# RFID_MODULE_S01.net
KiCad netlist of a schematic drawn in Altium Designer
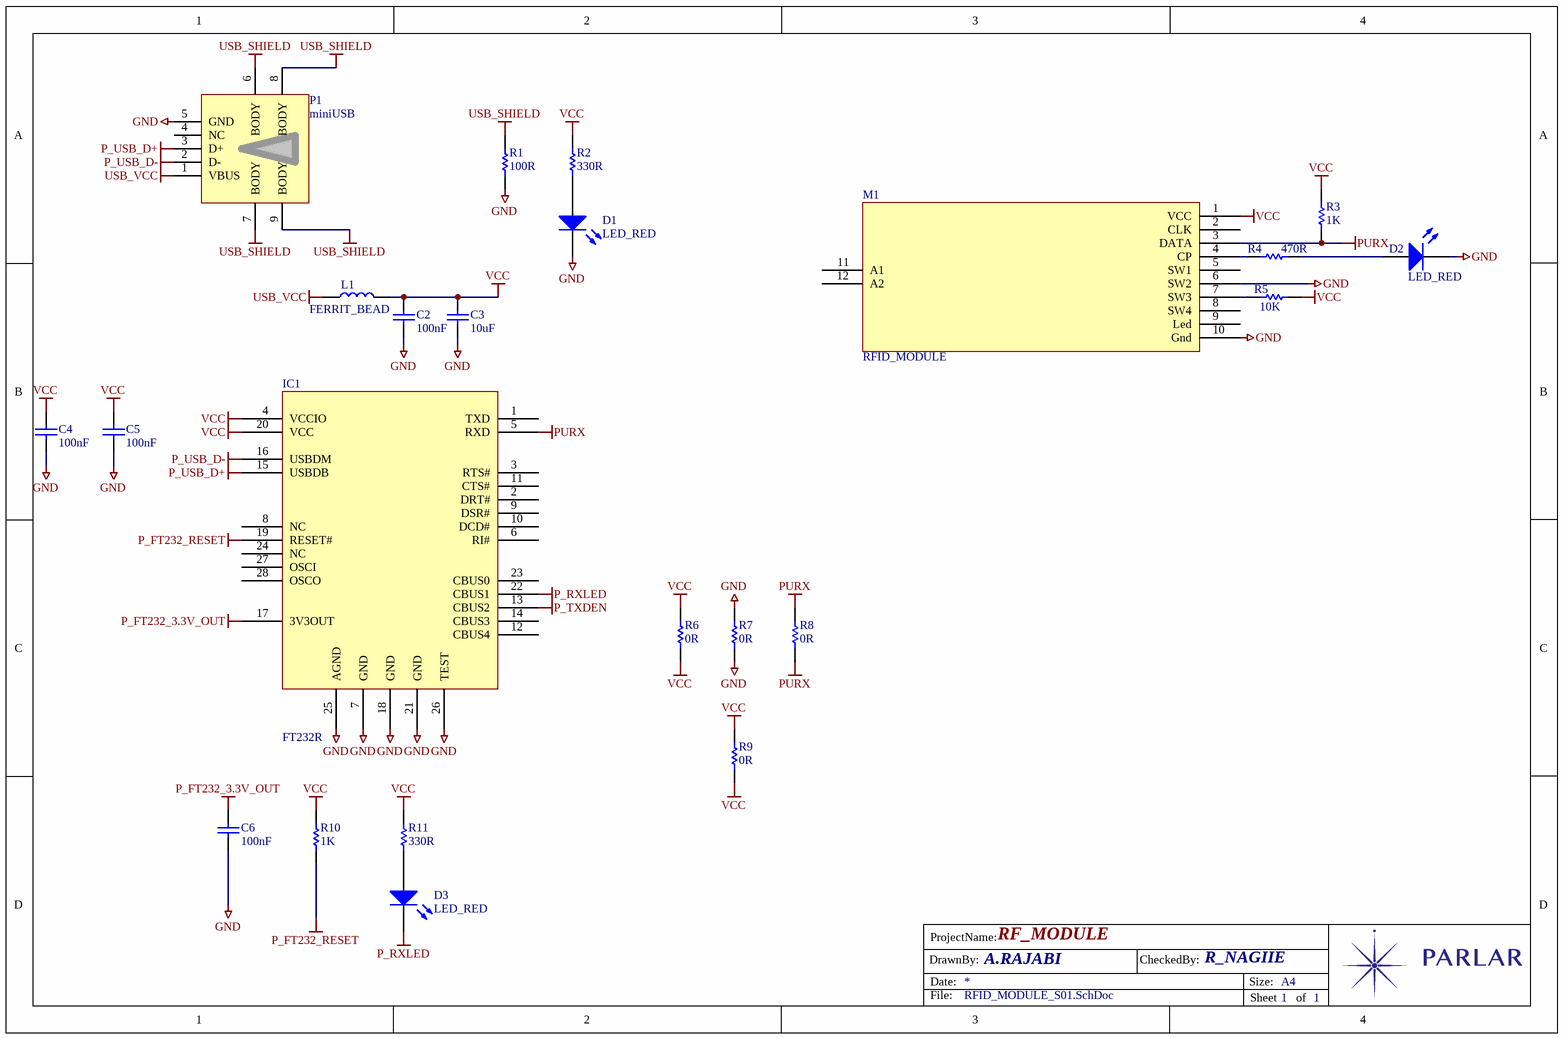
[diagram p0: RFID_MODULE_S01.SchDoc]

(export (version "E")
  (design (tool "Eeschema 10.0.6"))
  (components
    (comp (ref "C2")
      (value "100nF")
      (footprint "SMD 0805")
      (description "Capacitor")
      (fields (field (name "PUBLISHER") "Altium Limited"))
      (libsource (lib "Parlarlib_23") (part "CAP"))
    )
    (comp (ref "C3")
      (value "10uF")
      (footprint "SMD 0805")
      (description "Capacitor")
      (fields (field (name "PUBLISHER") "Altium Limited"))
      (libsource (lib "Parlarlib_23") (part "CAP"))
    )
    (comp (ref "C4")
      (value "100nF")
      (footprint "SMD 0805")
      (description "Capacitor")
      (fields (field (name "PUBLISHER") "Altium Limited"))
      (libsource (lib "Parlarlib_23") (part "CAP"))
    )
    (comp (ref "C5")
      (value "100nF")
      (footprint "SMD 1206")
      (description "Capacitor")
      (fields (field (name "PUBLISHER") "Altium Limited"))
      (libsource (lib "Parlarlib_23") (part "CAP"))
    )
    (comp (ref "C6")
      (value "100nF")
      (footprint "SMD 0805")
      (description "Capacitor")
      (fields (field (name "PUBLISHER") "Altium Limited"))
      (libsource (lib "Parlarlib_23") (part "CAP"))
    )
    (comp (ref "D1")
      (value "LED_RED")
      (footprint "SMD LED 0603")
      (description "Typical INFRARED GaAs LED")
      (fields (field (name "PUBLISHER") "Altium Limited"))
      (libsource (lib "Parlarlib_23") (part "LED"))
    )
    (comp (ref "D2")
      (value "LED_RED")
      (footprint "SMD LED 0603")
      (description "Typical INFRARED GaAs LED")
      (fields (field (name "PUBLISHER") "Altium Limited"))
      (libsource (lib "Parlarlib_23") (part "LED"))
    )
    (comp (ref "D3")
      (value "LED_RED")
      (footprint "SMD LED 0603")
      (description "Typical INFRARED GaAs LED")
      (fields (field (name "PUBLISHER") "Altium Limited"))
      (libsource (lib "Parlarlib_23") (part "LED"))
    )
    (comp (ref "IC1")
      (value "FT232R")
      (footprint "SMD IC SSOP28")
      (libsource (lib "Schlib1") (part "FT232R"))
    )
    (comp (ref "L1")
      (value "FERRIT_BEAD")
      (footprint "SMD 1206")
      (description "Inductor")
      (libsource (lib "Parlarlib_23") (part "INDUCTOR"))
    )
    (comp (ref "M1")
      (value "RFID_MODULE")
      (footprint "PCBComponent_1")
      (libsource (lib "Schlib1") (part "RFID_MODULE"))
    )
    (comp (ref "P1")
      (value "miniUSB")
      (footprint "SMD USB B MINI")
      (libsource (lib "Schlib1") (part "CON miniUSB Female SMD"))
    )
    (comp (ref "R1")
      (value "100R")
      (footprint "SMD 0805")
      (description "Resistor")
      (libsource (lib "Parlarlib_23") (part "RES"))
    )
    (comp (ref "R2")
      (value "330R")
      (footprint "SMD 1206")
      (description "Resistor")
      (libsource (lib "Parlarlib_23") (part "RES"))
    )
    (comp (ref "R3")
      (value "1K")
      (footprint "SMD 0805")
      (description "Resistor")
      (libsource (lib "Parlarlib_23") (part "RES"))
    )
    (comp (ref "R4")
      (value "470R")
      (footprint "SMD 0805")
      (description "Resistor")
      (libsource (lib "Parlarlib_23") (part "RES"))
    )
    (comp (ref "R5")
      (value "10K")
      (footprint "SMD 1206")
      (description "Resistor")
      (libsource (lib "Parlarlib_23") (part "RES"))
    )
    (comp (ref "R6")
      (value "0R")
      (footprint "SMD 1206")
      (description "Resistor")
      (libsource (lib "Parlarlib_23") (part "RES"))
    )
    (comp (ref "R7")
      (value "0R")
      (footprint "SMD 1206")
      (description "Resistor")
      (libsource (lib "Parlarlib_23") (part "RES"))
    )
    (comp (ref "R8")
      (value "0R")
      (footprint "SMD 1206")
      (description "Resistor")
      (libsource (lib "Parlarlib_23") (part "RES"))
    )
    (comp (ref "R9")
      (value "0R")
      (footprint "SMD 1206")
      (description "Resistor")
      (libsource (lib "Parlarlib_23") (part "RES"))
    )
    (comp (ref "R10")
      (value "1K")
      (footprint "SMD 0805")
      (description "Resistor")
      (libsource (lib "Parlarlib_23") (part "RES"))
    )
    (comp (ref "R11")
      (value "330R")
      (footprint "SMD 1206")
      (description "Resistor")
      (libsource (lib "Parlarlib_23") (part "RES"))
    )
  )
  (nets
    (net (code "1") (name "GND") (class "Default")
      (node (ref "C2") (pin "2") (pinfunction "2_2") (pintype "passive"))
      (node (ref "C3") (pin "2") (pinfunction "2_2") (pintype "passive"))
      (node (ref "C4") (pin "2") (pinfunction "2_2") (pintype "passive"))
      (node (ref "C5") (pin "2") (pinfunction "2_2") (pintype "passive"))
      (node (ref "C6") (pin "2") (pinfunction "2_2") (pintype "passive"))
      (node (ref "D1") (pin "2") (pinfunction "2_2") (pintype "passive"))
      (node (ref "D2") (pin "2") (pinfunction "2_2") (pintype "passive"))
      (node (ref "IC1") (pin "18") (pinfunction "GND_18") (pintype "passive"))
      (node (ref "IC1") (pin "21") (pinfunction "GND_21") (pintype "passive"))
      (node (ref "IC1") (pin "25") (pinfunction "AGND_25") (pintype "passive"))
      (node (ref "IC1") (pin "26") (pinfunction "TEST_26") (pintype "passive"))
      (node (ref "IC1") (pin "7") (pinfunction "GND_7") (pintype "passive"))
      (node (ref "M1") (pin "10") (pinfunction "Gnd_10") (pintype "passive"))
      (node (ref "M1") (pin "6") (pinfunction "SW2_6") (pintype "passive"))
      (node (ref "P1") (pin "5") (pinfunction "GND_5") (pintype "passive"))
      (node (ref "R1") (pin "1") (pinfunction "1_1") (pintype "passive"))
      (node (ref "R7") (pin "1") (pinfunction "1_1") (pintype "passive"))
      (node (ref "R7") (pin "2") (pinfunction "2_2") (pintype "passive"))
    )
    (net (code "2") (name "Net-(D1-Pad1)") (class "Default")
      (node (ref "D1") (pin "1") (pinfunction "1_1") (pintype "passive"))
      (node (ref "R2") (pin "1") (pinfunction "1_1") (pintype "passive"))
    )
    (net (code "3") (name "Net-(D2-Pad1)") (class "Default")
      (node (ref "D2") (pin "1") (pinfunction "1_1") (pintype "passive"))
      (node (ref "R4") (pin "2") (pinfunction "2_2") (pintype "passive"))
    )
    (net (code "4") (name "Net-(D3-Pad1)") (class "Default")
      (node (ref "D3") (pin "1") (pinfunction "1_1") (pintype "passive"))
      (node (ref "R11") (pin "1") (pinfunction "1_1") (pintype "passive"))
    )
    (net (code "5") (name "Net-(M1-CP)") (class "Default")
      (node (ref "M1") (pin "4") (pinfunction "CP_4") (pintype "passive"))
      (node (ref "R4") (pin "1") (pinfunction "1_1") (pintype "passive"))
    )
    (net (code "6") (name "Net-(M1-SW3)") (class "Default")
      (node (ref "M1") (pin "7") (pinfunction "SW3_7") (pintype "passive"))
      (node (ref "R5") (pin "1") (pinfunction "1_1") (pintype "passive"))
    )
    (net (code "7") (name "PURX") (class "Default")
      (node (ref "IC1") (pin "5") (pinfunction "RXD_5") (pintype "passive"))
      (node (ref "M1") (pin "3") (pinfunction "DATA_3") (pintype "passive"))
      (node (ref "R3") (pin "1") (pinfunction "1_1") (pintype "passive"))
      (node (ref "R8") (pin "1") (pinfunction "1_1") (pintype "passive"))
      (node (ref "R8") (pin "2") (pinfunction "2_2") (pintype "passive"))
    )
    (net (code "8") (name "P_FT232_3.3V_OUT") (class "Default")
      (node (ref "C6") (pin "1") (pinfunction "1_1") (pintype "passive"))
      (node (ref "IC1") (pin "17") (pinfunction "3V3OUT_17") (pintype "passive"))
    )
    (net (code "9") (name "P_FT232_RESET") (class "Default")
      (node (ref "IC1") (pin "19") (pinfunction "RESET#_19") (pintype "passive"))
      (node (ref "R10") (pin "1") (pinfunction "1_1") (pintype "passive"))
    )
    (net (code "10") (name "P_RXLED") (class "Default")
      (node (ref "D3") (pin "2") (pinfunction "2_2") (pintype "passive"))
      (node (ref "IC1") (pin "22") (pinfunction "CBUS1_22") (pintype "passive"))
    )
    (net (code "11") (name "P_TXDEN") (class "Default")
      (node (ref "IC1") (pin "13") (pinfunction "CBUS2_13") (pintype "passive"))
    )
    (net (code "12") (name "P_USB_D+") (class "Default")
      (node (ref "IC1") (pin "15") (pinfunction "USBDB_15") (pintype "passive"))
      (node (ref "P1") (pin "3") (pinfunction "D+_3") (pintype "passive"))
    )
    (net (code "13") (name "P_USB_D-") (class "Default")
      (node (ref "IC1") (pin "16") (pinfunction "USBDM_16") (pintype "passive"))
      (node (ref "P1") (pin "2") (pinfunction "D-_2") (pintype "passive"))
    )
    (net (code "14") (name "USB_SHIELD") (class "Default")
      (node (ref "P1") (pin "6") (pinfunction "BODY_6") (pintype "passive"))
      (node (ref "P1") (pin "7") (pinfunction "BODY_7") (pintype "passive"))
      (node (ref "P1") (pin "8") (pinfunction "BODY_8") (pintype "passive"))
      (node (ref "P1") (pin "9") (pinfunction "BODY_9") (pintype "passive"))
      (node (ref "R1") (pin "2") (pinfunction "2_2") (pintype "passive"))
    )
    (net (code "15") (name "USB_VCC") (class "Default")
      (node (ref "L1") (pin "1") (pinfunction "1_1") (pintype "passive"))
      (node (ref "P1") (pin "1") (pinfunction "VBUS_1") (pintype "passive"))
    )
    (net (code "16") (name "VCC") (class "Default")
      (node (ref "C2") (pin "1") (pinfunction "1_1") (pintype "passive"))
      (node (ref "C3") (pin "1") (pinfunction "1_1") (pintype "passive"))
      (node (ref "C4") (pin "1") (pinfunction "1_1") (pintype "passive"))
      (node (ref "C5") (pin "1") (pinfunction "1_1") (pintype "passive"))
      (node (ref "IC1") (pin "20") (pinfunction "VCC_20") (pintype "passive"))
      (node (ref "IC1") (pin "4") (pinfunction "VCCIO_4") (pintype "passive"))
      (node (ref "L1") (pin "2") (pinfunction "2_2") (pintype "passive"))
      (node (ref "M1") (pin "1") (pinfunction "VCC_1") (pintype "passive"))
      (node (ref "R10") (pin "2") (pinfunction "2_2") (pintype "passive"))
      (node (ref "R11") (pin "2") (pinfunction "2_2") (pintype "passive"))
      (node (ref "R2") (pin "2") (pinfunction "2_2") (pintype "passive"))
      (node (ref "R3") (pin "2") (pinfunction "2_2") (pintype "passive"))
      (node (ref "R5") (pin "2") (pinfunction "2_2") (pintype "passive"))
      (node (ref "R6") (pin "1") (pinfunction "1_1") (pintype "passive"))
      (node (ref "R6") (pin "2") (pinfunction "2_2") (pintype "passive"))
      (node (ref "R9") (pin "1") (pinfunction "1_1") (pintype "passive"))
      (node (ref "R9") (pin "2") (pinfunction "2_2") (pintype "passive"))
    )
    (net (code "17") (name "unconnected-(IC1-CBUS0-Pad23)") (class "Default")
      (node (ref "IC1") (pin "23") (pinfunction "CBUS0_23") (pintype "passive"))
    )
    (net (code "18") (name "unconnected-(IC1-CBUS3-Pad14)") (class "Default")
      (node (ref "IC1") (pin "14") (pinfunction "CBUS3_14") (pintype "passive"))
    )
    (net (code "19") (name "unconnected-(IC1-CBUS4-Pad12)") (class "Default")
      (node (ref "IC1") (pin "12") (pinfunction "CBUS4_12") (pintype "passive"))
    )
    (net (code "20") (name "unconnected-(IC1-CTS#-Pad11)") (class "Default")
      (node (ref "IC1") (pin "11") (pinfunction "CTS#_11") (pintype "passive"))
    )
    (net (code "21") (name "unconnected-(IC1-DCD#-Pad10)") (class "Default")
      (node (ref "IC1") (pin "10") (pinfunction "DCD#_10") (pintype "passive"))
    )
    (net (code "22") (name "unconnected-(IC1-DRT#-Pad2)") (class "Default")
      (node (ref "IC1") (pin "2") (pinfunction "DRT#_2") (pintype "passive"))
    )
    (net (code "23") (name "unconnected-(IC1-DSR#-Pad9)") (class "Default")
      (node (ref "IC1") (pin "9") (pinfunction "DSR#_9") (pintype "passive"))
    )
    (net (code "24") (name "unconnected-(IC1-NC-Pad8)") (class "Default")
      (node (ref "IC1") (pin "8") (pinfunction "NC_8") (pintype "passive"))
    )
    (net (code "25") (name "unconnected-(IC1-NC-Pad24)") (class "Default")
      (node (ref "IC1") (pin "24") (pinfunction "NC_24") (pintype "passive"))
    )
    (net (code "26") (name "unconnected-(IC1-OSCI-Pad27)") (class "Default")
      (node (ref "IC1") (pin "27") (pinfunction "OSCI_27") (pintype "passive"))
    )
    (net (code "27") (name "unconnected-(IC1-OSCO-Pad28)") (class "Default")
      (node (ref "IC1") (pin "28") (pinfunction "OSCO_28") (pintype "passive"))
    )
    (net (code "28") (name "unconnected-(IC1-RI#-Pad6)") (class "Default")
      (node (ref "IC1") (pin "6") (pinfunction "RI#_6") (pintype "passive"))
    )
    (net (code "29") (name "unconnected-(IC1-RTS#-Pad3)") (class "Default")
      (node (ref "IC1") (pin "3") (pinfunction "RTS#_3") (pintype "passive"))
    )
    (net (code "30") (name "unconnected-(IC1-TXD-Pad1)") (class "Default")
      (node (ref "IC1") (pin "1") (pinfunction "TXD_1") (pintype "passive"))
    )
    (net (code "31") (name "unconnected-(M1-A1-Pad11)") (class "Default")
      (node (ref "M1") (pin "11") (pinfunction "A1_11") (pintype "passive"))
    )
    (net (code "32") (name "unconnected-(M1-A2-Pad12)") (class "Default")
      (node (ref "M1") (pin "12") (pinfunction "A2_12") (pintype "passive"))
    )
    (net (code "33") (name "unconnected-(M1-CLK-Pad2)") (class "Default")
      (node (ref "M1") (pin "2") (pinfunction "CLK_2") (pintype "passive"))
    )
    (net (code "34") (name "unconnected-(M1-Led-Pad9)") (class "Default")
      (node (ref "M1") (pin "9") (pinfunction "Led_9") (pintype "passive"))
    )
    (net (code "35") (name "unconnected-(M1-SW1-Pad5)") (class "Default")
      (node (ref "M1") (pin "5") (pinfunction "SW1_5") (pintype "passive"))
    )
    (net (code "36") (name "unconnected-(M1-SW4-Pad8)") (class "Default")
      (node (ref "M1") (pin "8") (pinfunction "SW4_8") (pintype "passive"))
    )
    (net (code "37") (name "unconnected-(P1-NC-Pad4)") (class "Default")
      (node (ref "P1") (pin "4") (pinfunction "NC_4") (pintype "passive"))
    )
  )
)
